# PLD_AcessPortInterface.net
KiCad netlist of a schematic drawn in Altium Designer
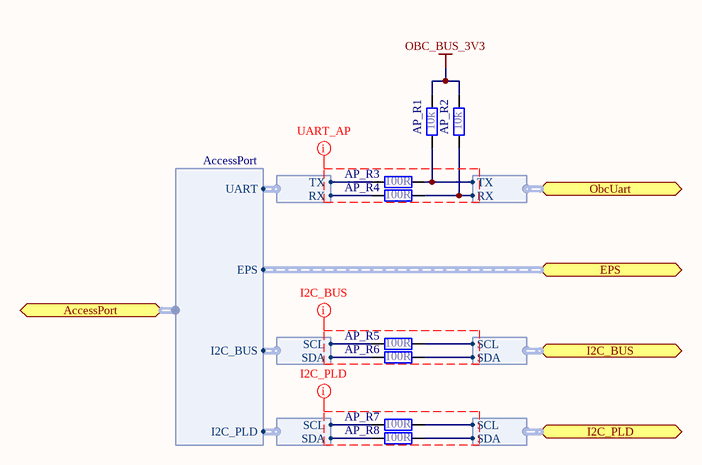
[diagram p0: PLD_AcessPortInterface.SchDoc]

(export (version "E")
  (design (tool "Eeschema 10.0.6"))
  (components
    (comp (ref "AP_R1") (value "10k") (footprint "SMD_Resistor_0603") (libsource (lib "") (part "Res_1")))
    (comp (ref "AP_R2") (value "10k") (footprint "SMD_Resistor_0603") (libsource (lib "") (part "Res_1")))
    (comp (ref "AP_R3")
      (value "100R")
      (footprint "SMD_Resistor_0603")
      (libsource (lib "resistors") (part "Res"))
    )
    (comp (ref "AP_R4")
      (value "100R")
      (footprint "SMD_Resistor_0603")
      (libsource (lib "resistors") (part "Res"))
    )
    (comp (ref "AP_R5")
      (value "100R")
      (footprint "SMD_Resistor_0603")
      (libsource (lib "resistors") (part "Res"))
    )
    (comp (ref "AP_R6")
      (value "100R")
      (footprint "SMD_Resistor_0603")
      (libsource (lib "resistors") (part "Res"))
    )
    (comp (ref "AP_R7")
      (value "100R")
      (footprint "SMD_Resistor_0603")
      (libsource (lib "resistors") (part "Res"))
    )
    (comp (ref "AP_R8")
      (value "100R")
      (footprint "SMD_Resistor_0603")
      (libsource (lib "resistors") (part "Res"))
    )
  )
  (nets
    (net (code "9") (name "Net-(AP_R1-Pad1)") (class "Default")
      (node (ref "AP_R1") (pin "1") (pinfunction "1_1") (pintype "passive"))
      (node (ref "AP_R3") (pin "2") (pinfunction "2_2") (pintype "passive"))
    )
    (net (code "10") (name "Net-(AP_R2-Pad1)") (class "Default")
      (node (ref "AP_R2") (pin "1") (pinfunction "1_1") (pintype "passive"))
      (node (ref "AP_R4") (pin "2") (pinfunction "2_2") (pintype "passive"))
    )
    (net (code "11") (name "OBC_BUS_3V3") (class "Default")
      (node (ref "AP_R1") (pin "2") (pinfunction "2_2") (pintype "passive"))
      (node (ref "AP_R2") (pin "2") (pinfunction "2_2") (pintype "passive"))
    )
    (net (code "12") (name "unconnected-(AP_R3-Pad1)") (class "Default")
      (node (ref "AP_R3") (pin "1") (pinfunction "1_1") (pintype "passive"))
    )
    (net (code "13") (name "unconnected-(AP_R4-Pad1)") (class "Default")
      (node (ref "AP_R4") (pin "1") (pinfunction "1_1") (pintype "passive"))
    )
    (net (code "14") (name "unconnected-(AP_R5-Pad1)") (class "Default")
      (node (ref "AP_R5") (pin "1") (pinfunction "1_1") (pintype "passive"))
    )
    (net (code "15") (name "unconnected-(AP_R5-Pad2)") (class "Default")
      (node (ref "AP_R5") (pin "2") (pinfunction "2_2") (pintype "passive"))
    )
    (net (code "16") (name "unconnected-(AP_R6-Pad1)") (class "Default")
      (node (ref "AP_R6") (pin "1") (pinfunction "1_1") (pintype "passive"))
    )
    (net (code "17") (name "unconnected-(AP_R6-Pad2)") (class "Default")
      (node (ref "AP_R6") (pin "2") (pinfunction "2_2") (pintype "passive"))
    )
    (net (code "18") (name "unconnected-(AP_R7-Pad1)") (class "Default")
      (node (ref "AP_R7") (pin "1") (pinfunction "1_1") (pintype "passive"))
    )
    (net (code "19") (name "unconnected-(AP_R7-Pad2)") (class "Default")
      (node (ref "AP_R7") (pin "2") (pinfunction "2_2") (pintype "passive"))
    )
    (net (code "20") (name "unconnected-(AP_R8-Pad1)") (class "Default")
      (node (ref "AP_R8") (pin "1") (pinfunction "1_1") (pintype "passive"))
    )
    (net (code "21") (name "unconnected-(AP_R8-Pad2)") (class "Default")
      (node (ref "AP_R8") (pin "2") (pinfunction "2_2") (pintype "passive"))
    )
  )
)
